# mint.net
KiCad netlist of a schematic drawn in EAGLE
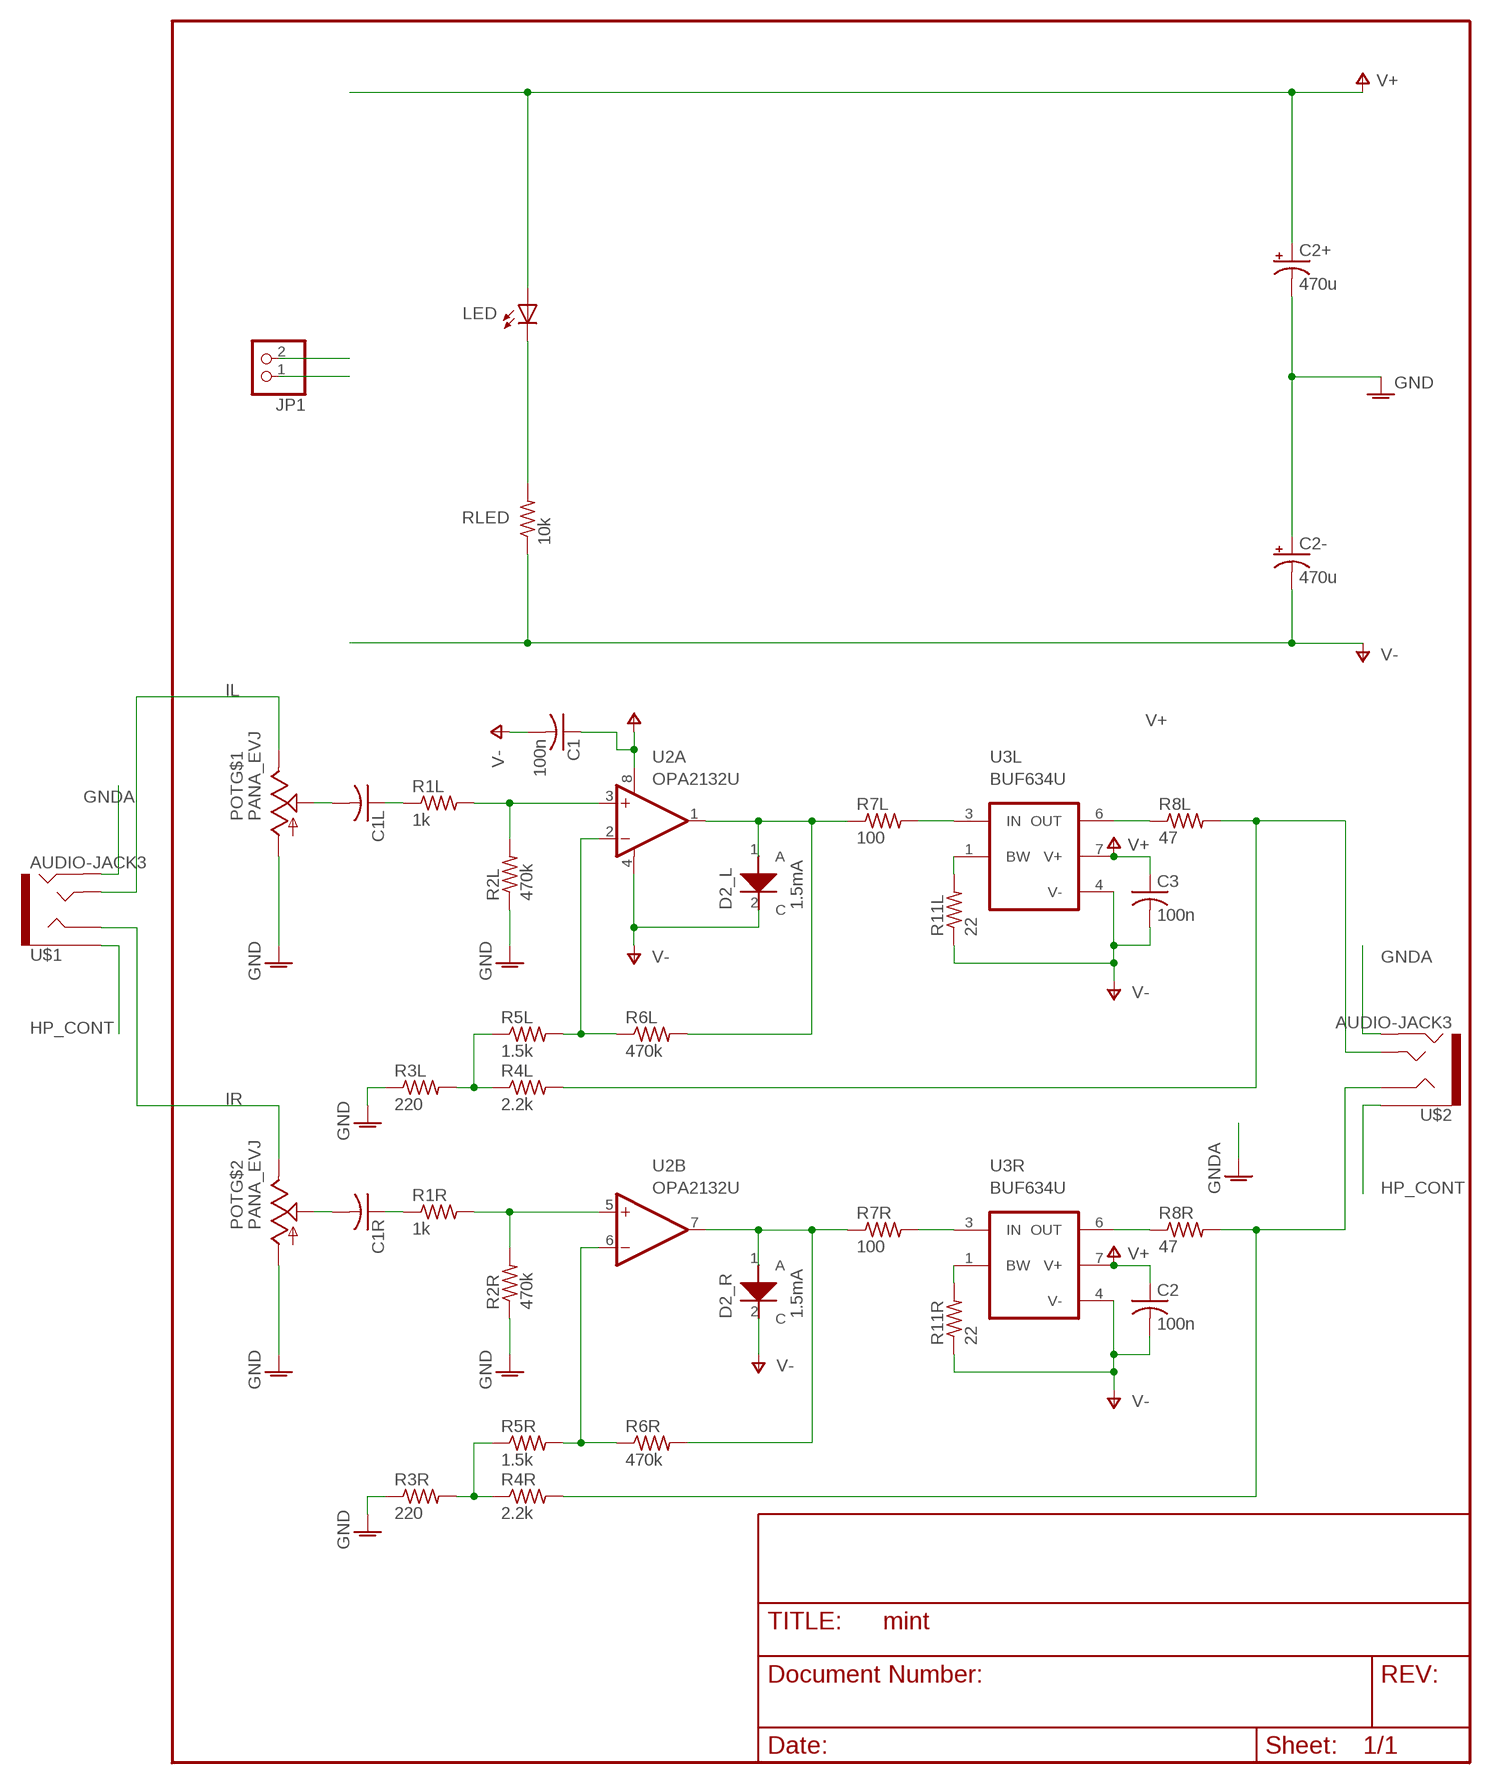
[diagram p0: schematic, sheet 1]

(export (version "E")
  (design (tool "Eeschema 10.0.6"))
  (components
    (comp (ref "C1")
      (value "100n")
      (footprint "eagle-import:C0603")
      (libsource (lib "eagle-import") (part "C-USC0603"))
    )
    (comp (ref "C1L")
      (value "C-USC1210")
      (footprint "eagle-import:C1210")
      (libsource (lib "eagle-import") (part "C-USC1210"))
    )
    (comp (ref "C1R")
      (value "C-USC1210")
      (footprint "eagle-import:C1210")
      (libsource (lib "eagle-import") (part "C-USC1210"))
    )
    (comp (ref "C2")
      (value "100n")
      (footprint "eagle-import:C0603")
      (libsource (lib "eagle-import") (part "C-USC0603"))
    )
    (comp (ref "C2+")
      (value "470u")
      (footprint "eagle-import:PANASONIC_G")
      (libsource (lib "eagle-import") (part "CPOL-USG"))
    )
    (comp (ref "C2-")
      (value "470u")
      (footprint "eagle-import:PANASONIC_G")
      (libsource (lib "eagle-import") (part "CPOL-USG"))
    )
    (comp (ref "C3")
      (value "100n")
      (footprint "eagle-import:C0603")
      (libsource (lib "eagle-import") (part "C-USC0603"))
    )
    (comp (ref "D2_L")
      (value "S-152T")
      (footprint "eagle-import:SMD-2616")
      (libsource (lib "eagle-import") (part "S-152T"))
    )
    (comp (ref "D2_R")
      (value "S-152T")
      (footprint "eagle-import:SMD-2616")
      (libsource (lib "eagle-import") (part "S-152T"))
    )
    (comp (ref "JP1")
      (value "PINHD-1X2")
      (footprint "eagle-import:1X02")
      (libsource (lib "eagle-import") (part "PINHD-1X2"))
    )
    (comp (ref "LED")
      (value "LEDCHIP-LED0603")
      (footprint "eagle-import:CHIP-LED0603")
      (libsource (lib "eagle-import") (part "LEDCHIP-LED0603"))
    )
    (comp (ref "POT")
      (value "PANA_EVJ")
      (footprint "eagle-import:ALPS_RK27")
      (libsource (lib "eagle-import") (part "ALPS_BLUE"))
    )
    (comp (ref "R1L")
      (value "1k")
      (footprint "eagle-import:R0603")
      (libsource (lib "eagle-import") (part "R-US_R0603"))
    )
    (comp (ref "R1R")
      (value "1k")
      (footprint "eagle-import:R0603")
      (libsource (lib "eagle-import") (part "R-US_R0603"))
    )
    (comp (ref "R2L")
      (value "470k")
      (footprint "eagle-import:R0603")
      (libsource (lib "eagle-import") (part "R-US_R0603"))
    )
    (comp (ref "R2R")
      (value "470k")
      (footprint "eagle-import:R0603")
      (libsource (lib "eagle-import") (part "R-US_R0603"))
    )
    (comp (ref "R3L")
      (value "220")
      (footprint "eagle-import:R0603")
      (libsource (lib "eagle-import") (part "R-US_R0603"))
    )
    (comp (ref "R3R")
      (value "220")
      (footprint "eagle-import:R0603")
      (libsource (lib "eagle-import") (part "R-US_R0603"))
    )
    (comp (ref "R4L")
      (value "2.2k")
      (footprint "eagle-import:R0603")
      (libsource (lib "eagle-import") (part "R-US_R0603"))
    )
    (comp (ref "R4R")
      (value "2.2k")
      (footprint "eagle-import:R0603")
      (libsource (lib "eagle-import") (part "R-US_R0603"))
    )
    (comp (ref "R5L")
      (value "1.5k")
      (footprint "eagle-import:R0603")
      (libsource (lib "eagle-import") (part "R-US_R0603"))
    )
    (comp (ref "R5R")
      (value "1.5k")
      (footprint "eagle-import:R0603")
      (libsource (lib "eagle-import") (part "R-US_R0603"))
    )
    (comp (ref "R6L")
      (value "470k")
      (footprint "eagle-import:R0603")
      (libsource (lib "eagle-import") (part "R-US_R0603"))
    )
    (comp (ref "R6R")
      (value "470k")
      (footprint "eagle-import:R0603")
      (libsource (lib "eagle-import") (part "R-US_R0603"))
    )
    (comp (ref "R7L")
      (value "100")
      (footprint "eagle-import:R0603")
      (libsource (lib "eagle-import") (part "R-US_R0603"))
    )
    (comp (ref "R7R")
      (value "100")
      (footprint "eagle-import:R0603")
      (libsource (lib "eagle-import") (part "R-US_R0603"))
    )
    (comp (ref "R8L")
      (value "47")
      (footprint "eagle-import:R0603")
      (libsource (lib "eagle-import") (part "R-US_R0603"))
    )
    (comp (ref "R8R")
      (value "47")
      (footprint "eagle-import:R0603")
      (libsource (lib "eagle-import") (part "R-US_R0603"))
    )
    (comp (ref "R11L")
      (value "22")
      (footprint "eagle-import:R0603")
      (libsource (lib "eagle-import") (part "R-US_R0603"))
    )
    (comp (ref "R11R")
      (value "22")
      (footprint "eagle-import:R0603")
      (libsource (lib "eagle-import") (part "R-US_R0603"))
    )
    (comp (ref "RLED")
      (value "10k")
      (footprint "eagle-import:R0603")
      (libsource (lib "eagle-import") (part "R-US_R0603"))
    )
    (comp (ref "U$1")
      (value "AUDIO-JACK3")
      (footprint "eagle-import:AUDIO-JACK-TRRS-SMD")
      (libsource (lib "eagle-import") (part "AUDIO-JACK3"))
    )
    (comp (ref "U$2")
      (value "AUDIO-JACK3")
      (footprint "eagle-import:AUDIO-JACK-TRRS-SMD")
      (libsource (lib "eagle-import") (part "AUDIO-JACK3"))
    )
    (comp (ref "U2")
      (value "OPA2132U")
      (footprint "eagle-import:SO08")
      (libsource (lib "eagle-import") (part "OPA2132U"))
    )
    (comp (ref "U3L")
      (value "BUF634U")
      (footprint "eagle-import:SO08")
      (libsource (lib "eagle-import") (part "BUF634U"))
    )
    (comp (ref "U3R")
      (value "BUF634U")
      (footprint "eagle-import:SO08")
      (libsource (lib "eagle-import") (part "BUF634U"))
    )
  )
  (nets
    (net (code "1") (name "/HP_CONT") (class "Default")
      (node (ref "U$1") (pin "EARTH") (pinfunction "EARTH_EARTH") (pintype "bidirectional"))
      (node (ref "U$2") (pin "EARTH") (pinfunction "EARTH_EARTH") (pintype "bidirectional"))
    )
    (net (code "2") (name "/IL") (class "Default")
      (node (ref "POT") (pin "I1") (pinfunction "3_I1") (pintype "passive"))
      (node (ref "U$1") (pin "TIP") (pinfunction "TIP_TIP") (pintype "bidirectional"))
    )
    (net (code "3") (name "/IR") (class "Default")
      (node (ref "POT") (pin "I2") (pinfunction "3_I2") (pintype "passive"))
      (node (ref "U$1") (pin "RING1") (pinfunction "RING1_RING1") (pintype "bidirectional"))
    )
    (net (code "4") (name "GND") (class "Default")
      (node (ref "C2+") (pin "-") (pinfunction "-_-") (pintype "passive"))
      (node (ref "C2-") (pin "+") (pinfunction "+_+") (pintype "passive"))
      (node (ref "POT") (pin "G1") (pinfunction "1_G1") (pintype "passive"))
      (node (ref "POT") (pin "G2") (pinfunction "1_G2") (pintype "passive"))
      (node (ref "R2L") (pin "1") (pinfunction "1_1") (pintype "passive"))
      (node (ref "R2R") (pin "1") (pinfunction "1_1") (pintype "passive"))
      (node (ref "R3L") (pin "1") (pinfunction "1_1") (pintype "passive"))
      (node (ref "R3R") (pin "1") (pinfunction "1_1") (pintype "passive"))
      (node (ref "U$1") (pin "RING2") (pinfunction "RING2_RING2") (pintype "bidirectional"))
      (node (ref "U$2") (pin "RING2") (pinfunction "RING2_RING2") (pintype "bidirectional"))
    )
    (net (code "5") (name "Net-(C1L-Pad1)") (class "Default")
      (node (ref "C1L") (pin "1") (pinfunction "1_1") (pintype "passive"))
      (node (ref "R1L") (pin "1") (pinfunction "1_1") (pintype "passive"))
    )
    (net (code "6") (name "Net-(C1R-Pad1)") (class "Default")
      (node (ref "C1R") (pin "1") (pinfunction "1_1") (pintype "passive"))
      (node (ref "R1R") (pin "1") (pinfunction "1_1") (pintype "passive"))
    )
    (net (code "7") (name "Net-(D2_L-A)") (class "Default")
      (node (ref "D2_L") (pin "1") (pinfunction "A_1") (pintype "bidirectional"))
      (node (ref "R6L") (pin "2") (pinfunction "2_2") (pintype "passive"))
      (node (ref "R7L") (pin "1") (pinfunction "1_1") (pintype "passive"))
      (node (ref "U2") (pin "1") (pinfunction "OUT_1") (pintype "output"))
    )
    (net (code "8") (name "Net-(D2_R-A)") (class "Default")
      (node (ref "D2_R") (pin "1") (pinfunction "A_1") (pintype "bidirectional"))
      (node (ref "R6R") (pin "2") (pinfunction "2_2") (pintype "passive"))
      (node (ref "R7R") (pin "1") (pinfunction "1_1") (pintype "passive"))
      (node (ref "U2") (pin "7") (pinfunction "OUT_7") (pintype "output"))
    )
    (net (code "9") (name "Net-(LED-PadC)") (class "Default")
      (node (ref "LED") (pin "C") (pinfunction "C_C") (pintype "passive"))
      (node (ref "RLED") (pin "2") (pinfunction "2_2") (pintype "passive"))
    )
    (net (code "10") (name "Net-(POTA-2)") (class "Default")
      (node (ref "C1L") (pin "2") (pinfunction "2_2") (pintype "passive"))
      (node (ref "POT") (pin "O1") (pinfunction "2_O1") (pintype "passive"))
    )
    (net (code "11") (name "Net-(POTB-2)") (class "Default")
      (node (ref "C1R") (pin "2") (pinfunction "2_2") (pintype "passive"))
      (node (ref "POT") (pin "O2") (pinfunction "2_O2") (pintype "passive"))
    )
    (net (code "12") (name "Net-(R3L-Pad2)") (class "Default")
      (node (ref "R3L") (pin "2") (pinfunction "2_2") (pintype "passive"))
      (node (ref "R4L") (pin "1") (pinfunction "1_1") (pintype "passive"))
      (node (ref "R5L") (pin "1") (pinfunction "1_1") (pintype "passive"))
    )
    (net (code "13") (name "Net-(R3R-Pad2)") (class "Default")
      (node (ref "R3R") (pin "2") (pinfunction "2_2") (pintype "passive"))
      (node (ref "R4R") (pin "1") (pinfunction "1_1") (pintype "passive"))
      (node (ref "R5R") (pin "1") (pinfunction "1_1") (pintype "passive"))
    )
    (net (code "14") (name "Net-(R4L-Pad2)") (class "Default")
      (node (ref "R4L") (pin "2") (pinfunction "2_2") (pintype "passive"))
      (node (ref "R8L") (pin "2") (pinfunction "2_2") (pintype "passive"))
      (node (ref "U$2") (pin "TIP") (pinfunction "TIP_TIP") (pintype "bidirectional"))
    )
    (net (code "15") (name "Net-(R4R-Pad2)") (class "Default")
      (node (ref "R4R") (pin "2") (pinfunction "2_2") (pintype "passive"))
      (node (ref "R8R") (pin "2") (pinfunction "2_2") (pintype "passive"))
      (node (ref "U$2") (pin "RING1") (pinfunction "RING1_RING1") (pintype "bidirectional"))
    )
    (net (code "16") (name "Net-(U2A-+IN)") (class "Default")
      (node (ref "R1L") (pin "2") (pinfunction "2_2") (pintype "passive"))
      (node (ref "R2L") (pin "2") (pinfunction "2_2") (pintype "passive"))
      (node (ref "U2") (pin "3") (pinfunction "+IN_3") (pintype "input"))
    )
    (net (code "17") (name "Net-(U2A--IN)") (class "Default")
      (node (ref "R5L") (pin "2") (pinfunction "2_2") (pintype "passive"))
      (node (ref "R6L") (pin "1") (pinfunction "1_1") (pintype "passive"))
      (node (ref "U2") (pin "2") (pinfunction "-IN_2") (pintype "input"))
    )
    (net (code "18") (name "Net-(U2B-+IN)") (class "Default")
      (node (ref "R1R") (pin "2") (pinfunction "2_2") (pintype "passive"))
      (node (ref "R2R") (pin "2") (pinfunction "2_2") (pintype "passive"))
      (node (ref "U2") (pin "5") (pinfunction "+IN_5") (pintype "input"))
    )
    (net (code "19") (name "Net-(U2B--IN)") (class "Default")
      (node (ref "R5R") (pin "2") (pinfunction "2_2") (pintype "passive"))
      (node (ref "R6R") (pin "1") (pinfunction "1_1") (pintype "passive"))
      (node (ref "U2") (pin "6") (pinfunction "-IN_6") (pintype "input"))
    )
    (net (code "20") (name "Net-(U3L-BW)") (class "Default")
      (node (ref "R11L") (pin "2") (pinfunction "2_2") (pintype "passive"))
      (node (ref "U3L") (pin "1") (pinfunction "BW_1") (pintype "passive"))
    )
    (net (code "21") (name "Net-(U3L-IN)") (class "Default")
      (node (ref "R7L") (pin "2") (pinfunction "2_2") (pintype "passive"))
      (node (ref "U3L") (pin "3") (pinfunction "IN_3") (pintype "input"))
    )
    (net (code "22") (name "Net-(U3L-OUT)") (class "Default")
      (node (ref "R8L") (pin "1") (pinfunction "1_1") (pintype "passive"))
      (node (ref "U3L") (pin "6") (pinfunction "OUT_6") (pintype "output"))
    )
    (net (code "23") (name "Net-(U3R-BW)") (class "Default")
      (node (ref "R11R") (pin "2") (pinfunction "2_2") (pintype "passive"))
      (node (ref "U3R") (pin "1") (pinfunction "BW_1") (pintype "passive"))
    )
    (net (code "24") (name "Net-(U3R-IN)") (class "Default")
      (node (ref "R7R") (pin "2") (pinfunction "2_2") (pintype "passive"))
      (node (ref "U3R") (pin "3") (pinfunction "IN_3") (pintype "input"))
    )
    (net (code "25") (name "Net-(U3R-OUT)") (class "Default")
      (node (ref "R8R") (pin "1") (pinfunction "1_1") (pintype "passive"))
      (node (ref "U3R") (pin "6") (pinfunction "OUT_6") (pintype "output"))
    )
    (net (code "26") (name "V+") (class "Default")
      (node (ref "C1") (pin "1") (pinfunction "1_1") (pintype "passive"))
      (node (ref "C2") (pin "1") (pinfunction "1_1") (pintype "passive"))
      (node (ref "C2+") (pin "+") (pinfunction "+_+") (pintype "passive"))
      (node (ref "C3") (pin "1") (pinfunction "1_1") (pintype "passive"))
      (node (ref "LED") (pin "A") (pinfunction "A_A") (pintype "passive"))
      (node (ref "U2") (pin "8") (pinfunction "V+_8") (pintype "power_in"))
      (node (ref "U3L") (pin "7") (pinfunction "V+_7") (pintype "power_in"))
      (node (ref "U3R") (pin "7") (pinfunction "V+_7") (pintype "power_in"))
    )
    (net (code "27") (name "V-") (class "Default")
      (node (ref "C1") (pin "2") (pinfunction "2_2") (pintype "passive"))
      (node (ref "C2") (pin "2") (pinfunction "2_2") (pintype "passive"))
      (node (ref "C2-") (pin "-") (pinfunction "-_-") (pintype "passive"))
      (node (ref "C3") (pin "2") (pinfunction "2_2") (pintype "passive"))
      (node (ref "D2_L") (pin "2") (pinfunction "C_2") (pintype "bidirectional"))
      (node (ref "D2_R") (pin "2") (pinfunction "C_2") (pintype "bidirectional"))
      (node (ref "R11L") (pin "1") (pinfunction "1_1") (pintype "passive"))
      (node (ref "R11R") (pin "1") (pinfunction "1_1") (pintype "passive"))
      (node (ref "RLED") (pin "1") (pinfunction "1_1") (pintype "passive"))
      (node (ref "U2") (pin "4") (pinfunction "V-_4") (pintype "power_in"))
      (node (ref "U3L") (pin "4") (pinfunction "V-_4") (pintype "power_in"))
      (node (ref "U3R") (pin "4") (pinfunction "V-_4") (pintype "power_in"))
    )
    (net (code "28") (name "unconnected-(JP1-Pad1)") (class "Default")
      (node (ref "JP1") (pin "1") (pinfunction "1_1") (pintype "passive"))
    )
    (net (code "29") (name "unconnected-(JP1-Pad2)") (class "Default")
      (node (ref "JP1") (pin "2") (pinfunction "2_2") (pintype "passive"))
    )
  )
)
